# meca_2013_2.net
KiCad netlist of a schematic drawn in EAGLE
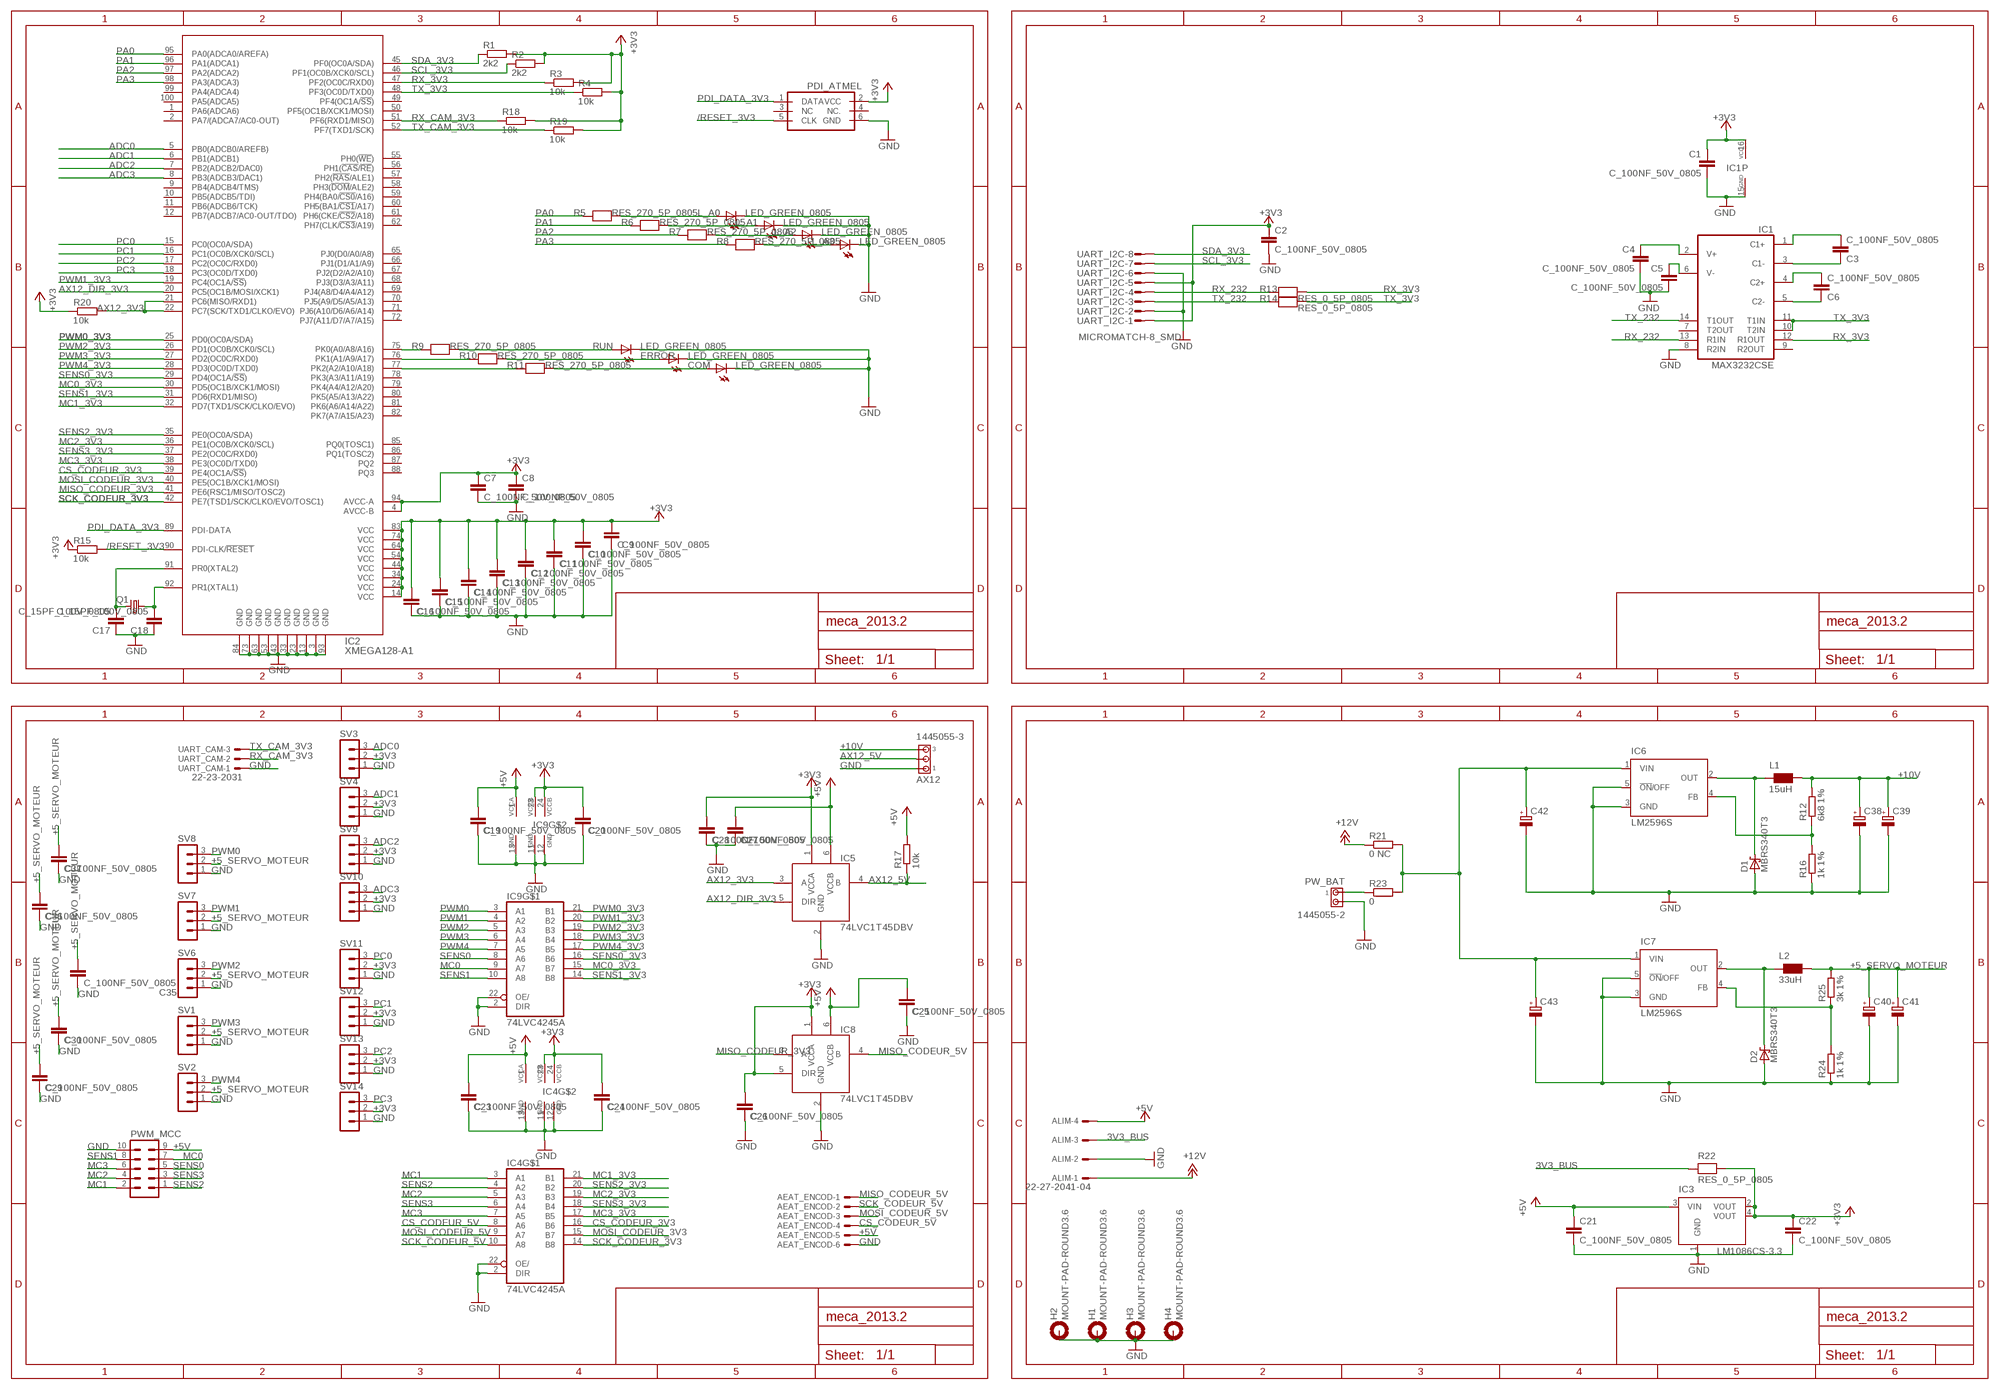
[diagram p0: schematic, sheet 1]

(export (version "E")
  (design (tool "Eeschema 10.0.6"))
  (components
    (comp (ref "AEAT_ENCOD")
      (value "22-23-2061")
      (footprint "eagle-import:22-23-2061")
      (fields (field (name "MF") "MOLEX"))
      (libsource (lib "eagle-import") (part "22-23-2061"))
    )
    (comp (ref "ALIM")
      (value "22-27-2041-04")
      (footprint "eagle-import:6410-04")
      (libsource (lib "eagle-import") (part "22-?-0427-2041"))
    )
    (comp (ref "AX12")
      (value "1445055-3")
      (footprint "eagle-import:1445055-3")
      (libsource (lib "eagle-import") (part "1445055-3"))
    )
    (comp (ref "C1")
      (value "C_100NF_50V_0805")
      (footprint "eagle-import:C0805")
      (libsource (lib "eagle-import") (part "C_100NF_50V_0805"))
    )
    (comp (ref "C2")
      (value "C_100NF_50V_0805")
      (footprint "eagle-import:C0805")
      (libsource (lib "eagle-import") (part "C_100NF_50V_0805"))
    )
    (comp (ref "C3")
      (value "C_100NF_50V_0805")
      (footprint "eagle-import:C0805")
      (libsource (lib "eagle-import") (part "C_100NF_50V_0805"))
    )
    (comp (ref "C4")
      (value "C_100NF_50V_0805")
      (footprint "eagle-import:C0805")
      (libsource (lib "eagle-import") (part "C_100NF_50V_0805"))
    )
    (comp (ref "C5")
      (value "C_100NF_50V_0805")
      (footprint "eagle-import:C0805")
      (libsource (lib "eagle-import") (part "C_100NF_50V_0805"))
    )
    (comp (ref "C6")
      (value "C_100NF_50V_0805")
      (footprint "eagle-import:C0805")
      (libsource (lib "eagle-import") (part "C_100NF_50V_0805"))
    )
    (comp (ref "C7")
      (value "C_100NF_50V_0805")
      (footprint "eagle-import:C0805")
      (libsource (lib "eagle-import") (part "C_100NF_50V_0805"))
    )
    (comp (ref "C8")
      (value "C_100NF_50V_0805")
      (footprint "eagle-import:C0805")
      (libsource (lib "eagle-import") (part "C_100NF_50V_0805"))
    )
    (comp (ref "C9")
      (value "C_100NF_50V_0805")
      (footprint "eagle-import:C0805")
      (libsource (lib "eagle-import") (part "C_100NF_50V_0805"))
    )
    (comp (ref "C10")
      (value "C_100NF_50V_0805")
      (footprint "eagle-import:C0805")
      (libsource (lib "eagle-import") (part "C_100NF_50V_0805"))
    )
    (comp (ref "C11")
      (value "C_100NF_50V_0805")
      (footprint "eagle-import:C0805")
      (libsource (lib "eagle-import") (part "C_100NF_50V_0805"))
    )
    (comp (ref "C12")
      (value "C_100NF_50V_0805")
      (footprint "eagle-import:C0805")
      (libsource (lib "eagle-import") (part "C_100NF_50V_0805"))
    )
    (comp (ref "C13")
      (value "C_100NF_50V_0805")
      (footprint "eagle-import:C0805")
      (libsource (lib "eagle-import") (part "C_100NF_50V_0805"))
    )
    (comp (ref "C14")
      (value "C_100NF_50V_0805")
      (footprint "eagle-import:C0805")
      (libsource (lib "eagle-import") (part "C_100NF_50V_0805"))
    )
    (comp (ref "C15")
      (value "C_100NF_50V_0805")
      (footprint "eagle-import:C0805")
      (libsource (lib "eagle-import") (part "C_100NF_50V_0805"))
    )
    (comp (ref "C16")
      (value "C_100NF_50V_0805")
      (footprint "eagle-import:C0805")
      (libsource (lib "eagle-import") (part "C_100NF_50V_0805"))
    )
    (comp (ref "C17")
      (value "C_15PF_100V_0805")
      (footprint "eagle-import:C0805")
      (libsource (lib "eagle-import") (part "C_15PF_100V_0805"))
    )
    (comp (ref "C18")
      (value "C_15PF_100V_0805")
      (footprint "eagle-import:C0805")
      (libsource (lib "eagle-import") (part "C_15PF_100V_0805"))
    )
    (comp (ref "C19")
      (value "C_100NF_50V_0805")
      (footprint "eagle-import:C0805")
      (libsource (lib "eagle-import") (part "C_100NF_50V_0805"))
    )
    (comp (ref "C20")
      (value "C_100NF_50V_0805")
      (footprint "eagle-import:C0805")
      (libsource (lib "eagle-import") (part "C_100NF_50V_0805"))
    )
    (comp (ref "C21")
      (value "C_100NF_50V_0805")
      (footprint "eagle-import:C0805")
      (libsource (lib "eagle-import") (part "C_100NF_50V_0805"))
    )
    (comp (ref "C22")
      (value "C_100NF_50V_0805")
      (footprint "eagle-import:C0805")
      (libsource (lib "eagle-import") (part "C_100NF_50V_0805"))
    )
    (comp (ref "C23")
      (value "C_100NF_50V_0805")
      (footprint "eagle-import:C0805")
      (libsource (lib "eagle-import") (part "C_100NF_50V_0805"))
    )
    (comp (ref "C24")
      (value "C_100NF_50V_0805")
      (footprint "eagle-import:C0805")
      (libsource (lib "eagle-import") (part "C_100NF_50V_0805"))
    )
    (comp (ref "C25")
      (value "C_100NF_50V_0805")
      (footprint "eagle-import:C0805")
      (libsource (lib "eagle-import") (part "C_100NF_50V_0805"))
    )
    (comp (ref "C26")
      (value "C_100NF_50V_0805")
      (footprint "eagle-import:C0805")
      (libsource (lib "eagle-import") (part "C_100NF_50V_0805"))
    )
    (comp (ref "C27")
      (value "C_100NF_50V_0805")
      (footprint "eagle-import:C0805")
      (libsource (lib "eagle-import") (part "C_100NF_50V_0805"))
    )
    (comp (ref "C28")
      (value "C_100NF_50V_0805")
      (footprint "eagle-import:C0805")
      (libsource (lib "eagle-import") (part "C_100NF_50V_0805"))
    )
    (comp (ref "C29")
      (value "C_100NF_50V_0805")
      (footprint "eagle-import:C0805")
      (libsource (lib "eagle-import") (part "C_100NF_50V_0805"))
    )
    (comp (ref "C30")
      (value "C_100NF_50V_0805")
      (footprint "eagle-import:C0805")
      (libsource (lib "eagle-import") (part "C_100NF_50V_0805"))
    )
    (comp (ref "C35")
      (value "C_100NF_50V_0805")
      (footprint "eagle-import:C0805")
      (libsource (lib "eagle-import") (part "C_100NF_50V_0805"))
    )
    (comp (ref "C36")
      (value "C_100NF_50V_0805")
      (footprint "eagle-import:C0805")
      (libsource (lib "eagle-import") (part "C_100NF_50V_0805"))
    )
    (comp (ref "C37")
      (value "C_100NF_50V_0805")
      (footprint "eagle-import:C0805")
      (libsource (lib "eagle-import") (part "C_100NF_50V_0805"))
    )
    (comp (ref "C38")
      (value "CPOL-EUG")
      (footprint "eagle-import:PANASONIC_G")
      (libsource (lib "eagle-import") (part "CPOL-EUG"))
    )
    (comp (ref "C39")
      (value "CPOL-EUG")
      (footprint "eagle-import:PANASONIC_G")
      (libsource (lib "eagle-import") (part "CPOL-EUG"))
    )
    (comp (ref "C40")
      (value "CPOL-EUG")
      (footprint "eagle-import:PANASONIC_G")
      (libsource (lib "eagle-import") (part "CPOL-EUG"))
    )
    (comp (ref "C41")
      (value "CPOL-EUG")
      (footprint "eagle-import:PANASONIC_G")
      (libsource (lib "eagle-import") (part "CPOL-EUG"))
    )
    (comp (ref "C42")
      (value "CPOL-EUG")
      (footprint "eagle-import:PANASONIC_G")
      (libsource (lib "eagle-import") (part "CPOL-EUG"))
    )
    (comp (ref "C43")
      (value "CPOL-EUG")
      (footprint "eagle-import:PANASONIC_G")
      (libsource (lib "eagle-import") (part "CPOL-EUG"))
    )
    (comp (ref "COM")
      (value "LED_GREEN_0805")
      (footprint "eagle-import:CHIP-LED0805")
      (libsource (lib "eagle-import") (part "LED_GREEN_0805"))
    )
    (comp (ref "D1")
      (value "MBRS340T3")
      (footprint "eagle-import:SMC")
      (libsource (lib "eagle-import") (part "MBRS30T34"))
    )
    (comp (ref "D2")
      (value "MBRS340T3")
      (footprint "eagle-import:SMC")
      (libsource (lib "eagle-import") (part "MBRS30T34"))
    )
    (comp (ref "ERROR")
      (value "LED_GREEN_0805")
      (footprint "eagle-import:CHIP-LED0805")
      (libsource (lib "eagle-import") (part "LED_GREEN_0805"))
    )
    (comp (ref "H1")
      (value "MOUNT-PAD-ROUND3.6")
      (footprint "eagle-import:3,6-PAD")
      (libsource (lib "eagle-import") (part "MOUNT-PAD-ROUND3.6"))
    )
    (comp (ref "H2")
      (value "MOUNT-PAD-ROUND3.6")
      (footprint "eagle-import:3,6-PAD")
      (libsource (lib "eagle-import") (part "MOUNT-PAD-ROUND3.6"))
    )
    (comp (ref "H3")
      (value "MOUNT-PAD-ROUND3.6")
      (footprint "eagle-import:3,6-PAD")
      (libsource (lib "eagle-import") (part "MOUNT-PAD-ROUND3.6"))
    )
    (comp (ref "H4")
      (value "MOUNT-PAD-ROUND3.6")
      (footprint "eagle-import:3,6-PAD")
      (libsource (lib "eagle-import") (part "MOUNT-PAD-ROUND3.6"))
    )
    (comp (ref "IC1")
      (value "MAX3232CSE")
      (footprint "eagle-import:SO16")
      (libsource (lib "eagle-import") (part "MAX3232SEC"))
    )
    (comp (ref "IC2")
      (value "XMEGA128-A1")
      (footprint "eagle-import:TQFP100")
      (libsource (lib "eagle-import") (part "XMEGA-A1TQFP"))
    )
    (comp (ref "IC3")
      (value "LM1086CS-3.3")
      (footprint "eagle-import:TO263")
      (libsource (lib "eagle-import") (part "LM1086CS-3.3"))
    )
    (comp (ref "IC4")
      (value "74LVC4245A")
      (footprint "eagle-import:TSSOP28")
      (libsource (lib "eagle-import") (part "74LVC4245A"))
    )
    (comp (ref "IC5")
      (value "74LVC1T45DBV")
      (footprint "eagle-import:SOT23-6")
      (libsource (lib "eagle-import") (part "74LVC1T45DBV"))
    )
    (comp (ref "IC6")
      (value "LM2596S")
      (footprint "eagle-import:TO263-5")
      (fields (field (name "MF") "NATIONAL SEMICONDUCTOR") (field (name "MPN") "LM2596S-ADJ/NOPB"))
      (libsource (lib "eagle-import") (part "LM2596S"))
    )
    (comp (ref "IC7")
      (value "LM2596S")
      (footprint "eagle-import:TO263-5")
      (fields (field (name "MF") "NATIONAL SEMICONDUCTOR") (field (name "MPN") "LM2596S-ADJ/NOPB"))
      (libsource (lib "eagle-import") (part "LM2596S"))
    )
    (comp (ref "IC8")
      (value "74LVC1T45DBV")
      (footprint "eagle-import:SOT23-6")
      (libsource (lib "eagle-import") (part "74LVC1T45DBV"))
    )
    (comp (ref "IC9")
      (value "74LVC4245A")
      (footprint "eagle-import:TSSOP28")
      (libsource (lib "eagle-import") (part "74LVC4245A"))
    )
    (comp (ref "L1")
      (value "15uH")
      (footprint "eagle-import:WE-PD_L_XL_XXL")
      (libsource (lib "eagle-import") (part "WE-PD_L/XL/XXL"))
    )
    (comp (ref "L2")
      (value "33uH")
      (footprint "eagle-import:WE-PD_L_XL_XXL")
      (libsource (lib "eagle-import") (part "WE-PD_L/XL/XXL"))
    )
    (comp (ref "L_A0")
      (value "LED_GREEN_0805")
      (footprint "eagle-import:CHIP-LED0805")
      (libsource (lib "eagle-import") (part "LED_GREEN_0805"))
    )
    (comp (ref "L_A1")
      (value "LED_GREEN_0805")
      (footprint "eagle-import:CHIP-LED0805")
      (libsource (lib "eagle-import") (part "LED_GREEN_0805"))
    )
    (comp (ref "L_A2")
      (value "LED_GREEN_0805")
      (footprint "eagle-import:CHIP-LED0805")
      (libsource (lib "eagle-import") (part "LED_GREEN_0805"))
    )
    (comp (ref "L_A3")
      (value "LED_GREEN_0805")
      (footprint "eagle-import:CHIP-LED0805")
      (libsource (lib "eagle-import") (part "LED_GREEN_0805"))
    )
    (comp (ref "PDI_ATMEL")
      (value "PDI_ATMEL")
      (footprint "eagle-import:ML6")
      (libsource (lib "eagle-import") (part "PDI_ATMEL"))
    )
    (comp (ref "PWM_MCC")
      (value "ML10")
      (footprint "eagle-import:ML10")
      (libsource (lib "eagle-import") (part "ML10"))
    )
    (comp (ref "PW_BAT")
      (value "1445055-2")
      (footprint "eagle-import:1445055-2")
      (libsource (lib "eagle-import") (part "1445055-2"))
    )
    (comp (ref "Q1")
      (value "CRYSTAL_16MHZ_HC49UP")
      (footprint "eagle-import:HC49UP")
      (libsource (lib "eagle-import") (part "CRYSTAL_16MHZ_HC49UP"))
    )
    (comp (ref "R1")
      (value "2k2")
      (footprint "eagle-import:R0603")
      (libsource (lib "eagle-import") (part "R-EU_R0603"))
    )
    (comp (ref "R2")
      (value "2k2")
      (footprint "eagle-import:R0603")
      (libsource (lib "eagle-import") (part "R-EU_R0603"))
    )
    (comp (ref "R3")
      (value "10k")
      (footprint "eagle-import:R0603")
      (libsource (lib "eagle-import") (part "R-EU_R0603"))
    )
    (comp (ref "R4")
      (value "10k")
      (footprint "eagle-import:R0603")
      (libsource (lib "eagle-import") (part "R-EU_R0603"))
    )
    (comp (ref "R5")
      (value "RES_270_5P_0805")
      (footprint "eagle-import:R0805")
      (libsource (lib "eagle-import") (part "RES_270_5P_0805"))
    )
    (comp (ref "R6")
      (value "RES_270_5P_0805")
      (footprint "eagle-import:R0805")
      (libsource (lib "eagle-import") (part "RES_270_5P_0805"))
    )
    (comp (ref "R7")
      (value "RES_270_5P_0805")
      (footprint "eagle-import:R0805")
      (libsource (lib "eagle-import") (part "RES_270_5P_0805"))
    )
    (comp (ref "R8")
      (value "RES_270_5P_0805")
      (footprint "eagle-import:R0805")
      (libsource (lib "eagle-import") (part "RES_270_5P_0805"))
    )
    (comp (ref "R9")
      (value "RES_270_5P_0805")
      (footprint "eagle-import:R0805")
      (libsource (lib "eagle-import") (part "RES_270_5P_0805"))
    )
    (comp (ref "R10")
      (value "RES_270_5P_0805")
      (footprint "eagle-import:R0805")
      (libsource (lib "eagle-import") (part "RES_270_5P_0805"))
    )
    (comp (ref "R11")
      (value "RES_270_5P_0805")
      (footprint "eagle-import:R0805")
      (libsource (lib "eagle-import") (part "RES_270_5P_0805"))
    )
    (comp (ref "R12")
      (value "6k8 1%")
      (footprint "eagle-import:R0805")
      (libsource (lib "eagle-import") (part "resistor_R-EU_R0805"))
    )
    (comp (ref "R13")
      (value "RES_0_5P_0805")
      (footprint "eagle-import:R0805")
      (libsource (lib "eagle-import") (part "RES_0_5P_0805"))
    )
    (comp (ref "R14")
      (value "RES_0_5P_0805")
      (footprint "eagle-import:R0805")
      (libsource (lib "eagle-import") (part "RES_0_5P_0805"))
    )
    (comp (ref "R15")
      (value "10k")
      (footprint "eagle-import:R0603")
      (libsource (lib "eagle-import") (part "R-EU_R0603"))
    )
    (comp (ref "R16")
      (value "1k 1%")
      (footprint "eagle-import:R0805")
      (libsource (lib "eagle-import") (part "resistor_R-EU_R0805"))
    )
    (comp (ref "R17")
      (value "10k")
      (footprint "eagle-import:R0805")
      (libsource (lib "eagle-import") (part "resistor_R-EU_R0805"))
    )
    (comp (ref "R18")
      (value "10k")
      (footprint "eagle-import:R0603")
      (libsource (lib "eagle-import") (part "R-EU_R0603"))
    )
    (comp (ref "R19")
      (value "10k")
      (footprint "eagle-import:R0603")
      (libsource (lib "eagle-import") (part "R-EU_R0603"))
    )
    (comp (ref "R20")
      (value "10k")
      (footprint "eagle-import:R0603")
      (libsource (lib "eagle-import") (part "R-EU_R0603"))
    )
    (comp (ref "R21")
      (value "0 NC")
      (footprint "eagle-import:R0805")
      (libsource (lib "eagle-import") (part "R-EU_R0805"))
    )
    (comp (ref "R22")
      (value "RES_0_5P_0805")
      (footprint "eagle-import:R0805")
      (libsource (lib "eagle-import") (part "RES_0_5P_0805"))
    )
    (comp (ref "R23")
      (value "0")
      (footprint "eagle-import:R0805")
      (libsource (lib "eagle-import") (part "R-EU_R0805"))
    )
    (comp (ref "R24")
      (value "1k 1%")
      (footprint "eagle-import:R0805")
      (libsource (lib "eagle-import") (part "R-EU_R0805"))
    )
    (comp (ref "R25")
      (value "3k 1%")
      (footprint "eagle-import:R0805")
      (libsource (lib "eagle-import") (part "R-EU_R0805"))
    )
    (comp (ref "RUN")
      (value "LED_GREEN_0805")
      (footprint "eagle-import:CHIP-LED0805")
      (libsource (lib "eagle-import") (part "LED_GREEN_0805"))
    )
    (comp (ref "SV1")
      (value "MA03-1")
      (footprint "eagle-import:MA03-1")
      (libsource (lib "eagle-import") (part "MA03-1"))
    )
    (comp (ref "SV2")
      (value "MA03-1")
      (footprint "eagle-import:MA03-1")
      (libsource (lib "eagle-import") (part "MA03-1"))
    )
    (comp (ref "SV3")
      (value "MA03-1")
      (footprint "eagle-import:MA03-1")
      (fields (field (name "OC_FARNELL") "unknown") (field (name "OC_NEWARK") "unknown"))
      (libsource (lib "eagle-import") (part "MA03-1"))
    )
    (comp (ref "SV4")
      (value "MA03-1")
      (footprint "eagle-import:MA03-1")
      (fields (field (name "OC_FARNELL") "unknown") (field (name "OC_NEWARK") "unknown"))
      (libsource (lib "eagle-import") (part "MA03-1"))
    )
    (comp (ref "SV6")
      (value "MA03-1")
      (footprint "eagle-import:MA03-1")
      (fields (field (name "OC_FARNELL") "unknown") (field (name "OC_NEWARK") "unknown"))
      (libsource (lib "eagle-import") (part "MA03-1"))
    )
    (comp (ref "SV7")
      (value "MA03-1")
      (footprint "eagle-import:MA03-1")
      (fields (field (name "OC_FARNELL") "unknown") (field (name "OC_NEWARK") "unknown"))
      (libsource (lib "eagle-import") (part "MA03-1"))
    )
    (comp (ref "SV8")
      (value "MA03-1")
      (footprint "eagle-import:MA03-1")
      (fields (field (name "OC_FARNELL") "unknown") (field (name "OC_NEWARK") "unknown"))
      (libsource (lib "eagle-import") (part "MA03-1"))
    )
    (comp (ref "SV9")
      (value "MA03-1")
      (footprint "eagle-import:MA03-1")
      (fields (field (name "OC_FARNELL") "unknown") (field (name "OC_NEWARK") "unknown"))
      (libsource (lib "eagle-import") (part "MA03-1"))
    )
    (comp (ref "SV10")
      (value "MA03-1")
      (footprint "eagle-import:MA03-1")
      (fields (field (name "OC_FARNELL") "unknown") (field (name "OC_NEWARK") "unknown"))
      (libsource (lib "eagle-import") (part "MA03-1"))
    )
    (comp (ref "SV11")
      (value "MA03-1")
      (footprint "eagle-import:MA03-1")
      (fields (field (name "OC_FARNELL") "unknown") (field (name "OC_NEWARK") "unknown"))
      (libsource (lib "eagle-import") (part "MA03-1"))
    )
    (comp (ref "SV12")
      (value "MA03-1")
      (footprint "eagle-import:MA03-1")
      (fields (field (name "OC_FARNELL") "unknown") (field (name "OC_NEWARK") "unknown"))
      (libsource (lib "eagle-import") (part "MA03-1"))
    )
    (comp (ref "SV13")
      (value "MA03-1")
      (footprint "eagle-import:MA03-1")
      (fields (field (name "OC_FARNELL") "unknown") (field (name "OC_NEWARK") "unknown"))
      (libsource (lib "eagle-import") (part "MA03-1"))
    )
    (comp (ref "SV14")
      (value "MA03-1")
      (footprint "eagle-import:MA03-1")
      (fields (field (name "OC_FARNELL") "unknown") (field (name "OC_NEWARK") "unknown"))
      (libsource (lib "eagle-import") (part "MA03-1"))
    )
    (comp (ref "UART_CAM")
      (value "22-23-2031")
      (footprint "eagle-import:22-23-2031")
      (fields (field (name "MF") "MOLEX"))
      (libsource (lib "eagle-import") (part "22-23-2031"))
    )
    (comp (ref "UART_I2C")
      (value "MICROMATCH-8_SMD")
      (footprint "eagle-import:MICROMATCH-8_SMD")
      (libsource (lib "eagle-import") (part "MICROMATCH-8_SMD"))
    )
  )
  (nets
    (net (code "1") (name "+3V3") (class "Default")
      (node (ref "C1") (pin "1") (pinfunction "1_1") (pintype "passive"))
      (node (ref "C10") (pin "1") (pinfunction "1_1") (pintype "passive"))
      (node (ref "C11") (pin "1") (pinfunction "1_1") (pintype "passive"))
      (node (ref "C12") (pin "1") (pinfunction "1_1") (pintype "passive"))
      (node (ref "C13") (pin "1") (pinfunction "1_1") (pintype "passive"))
      (node (ref "C14") (pin "1") (pinfunction "1_1") (pintype "passive"))
      (node (ref "C15") (pin "1") (pinfunction "1_1") (pintype "passive"))
      (node (ref "C16") (pin "1") (pinfunction "1_1") (pintype "passive"))
      (node (ref "C2") (pin "1") (pinfunction "1_1") (pintype "passive"))
      (node (ref "C20") (pin "1") (pinfunction "1_1") (pintype "passive"))
      (node (ref "C22") (pin "1") (pinfunction "1_1") (pintype "passive"))
      (node (ref "C24") (pin "1") (pinfunction "1_1") (pintype "passive"))
      (node (ref "C26") (pin "1") (pinfunction "1_1") (pintype "passive"))
      (node (ref "C28") (pin "1") (pinfunction "1_1") (pintype "passive"))
      (node (ref "C7") (pin "1") (pinfunction "1_1") (pintype "passive"))
      (node (ref "C8") (pin "1") (pinfunction "1_1") (pintype "passive"))
      (node (ref "C9") (pin "1") (pinfunction "1_1") (pintype "passive"))
      (node (ref "IC1") (pin "16") (pinfunction "VCC_16") (pintype "power_in"))
      (node (ref "IC2") (pin "14") (pinfunction "VCC_14") (pintype "power_in"))
      (node (ref "IC2") (pin "24") (pinfunction "VCC_24") (pintype "power_in"))
      (node (ref "IC2") (pin "34") (pinfunction "VCC_34") (pintype "power_in"))
      (node (ref "IC2") (pin "4") (pinfunction "AVCC-B_4") (pintype "power_in"))
      (node (ref "IC2") (pin "44") (pinfunction "VCC_44") (pintype "power_in"))
      (node (ref "IC2") (pin "54") (pinfunction "VCC_54") (pintype "power_in"))
      (node (ref "IC2") (pin "64") (pinfunction "VCC_64") (pintype "power_in"))
      (node (ref "IC2") (pin "74") (pinfunction "VCC_74") (pintype "power_in"))
      (node (ref "IC2") (pin "83") (pinfunction "VCC_83") (pintype "power_in"))
      (node (ref "IC2") (pin "94") (pinfunction "AVCC-A_94") (pintype "power_in"))
      (node (ref "IC3") (pin "2") (pinfunction "VOUT_2") (pintype "bidirectional"))
      (node (ref "IC3") (pin "4") (pinfunction "VOUT_4") (pintype "bidirectional"))
      (node (ref "IC4") (pin "23") (pinfunction "VCCB_23") (pintype "power_in"))
      (node (ref "IC4") (pin "24") (pinfunction "VCCB_24") (pintype "power_in"))
      (node (ref "IC5") (pin "1") (pinfunction "VCCA_1") (pintype "power_in"))
      (node (ref "IC8") (pin "1") (pinfunction "VCCA_1") (pintype "power_in"))
      (node (ref "IC8") (pin "5") (pinfunction "DIR_5") (pintype "input"))
      (node (ref "IC9") (pin "23") (pinfunction "VCCB_23") (pintype "power_in"))
      (node (ref "IC9") (pin "24") (pinfunction "VCCB_24") (pintype "power_in"))
      (node (ref "PDI_ATMEL") (pin "2") (pinfunction "VCC_2") (pintype "passive"))
      (node (ref "R1") (pin "2") (pinfunction "2_2") (pintype "passive"))
      (node (ref "R15") (pin "1") (pinfunction "1_1") (pintype "passive"))
      (node (ref "R18") (pin "2") (pinfunction "2_2") (pintype "passive"))
      (node (ref "R19") (pin "2") (pinfunction "2_2") (pintype "passive"))
      (node (ref "R2") (pin "2") (pinfunction "2_2") (pintype "passive"))
      (node (ref "R20") (pin "1") (pinfunction "1_1") (pintype "passive"))
      (node (ref "R22") (pin "2") (pinfunction "2_2") (pintype "bidirectional"))
      (node (ref "R3") (pin "2") (pinfunction "2_2") (pintype "passive"))
      (node (ref "R4") (pin "2") (pinfunction "2_2") (pintype "passive"))
      (node (ref "SV10") (pin "2") (pinfunction "2_2") (pintype "passive"))
      (node (ref "SV11") (pin "2") (pinfunction "2_2") (pintype "passive"))
      (node (ref "SV12") (pin "2") (pinfunction "2_2") (pintype "passive"))
      (node (ref "SV13") (pin "2") (pinfunction "2_2") (pintype "passive"))
      (node (ref "SV14") (pin "2") (pinfunction "2_2") (pintype "passive"))
      (node (ref "SV3") (pin "2") (pinfunction "2_2") (pintype "passive"))
      (node (ref "SV4") (pin "2") (pinfunction "2_2") (pintype "passive"))
      (node (ref "SV9") (pin "2") (pinfunction "2_2") (pintype "passive"))
      (node (ref "UART_I2C") (pin "1") (pinfunction "S_1") (pintype "passive"))
      (node (ref "UART_I2C") (pin "5") (pinfunction "S_5") (pintype "passive"))
    )
    (net (code "2") (name "+5V") (class "Default")
      (node (ref "AEAT_ENCOD") (pin "5") (pinfunction "S_5") (pintype "passive"))
      (node (ref "ALIM") (pin "4") (pinfunction "S_4") (pintype "passive"))
      (node (ref "C19") (pin "1") (pinfunction "1_1") (pintype "passive"))
      (node (ref "C21") (pin "1") (pinfunction "1_1") (pintype "passive"))
      (node (ref "C23") (pin "1") (pinfunction "1_1") (pintype "passive"))
      (node (ref "C25") (pin "1") (pinfunction "1_1") (pintype "passive"))
      (node (ref "C27") (pin "1") (pinfunction "1_1") (pintype "passive"))
      (node (ref "IC3") (pin "3") (pinfunction "VIN_3") (pintype "bidirectional"))
      (node (ref "IC4") (pin "1") (pinfunction "VCCA_1") (pintype "power_in"))
      (node (ref "IC5") (pin "6") (pinfunction "VCCB_6") (pintype "power_in"))
      (node (ref "IC8") (pin "6") (pinfunction "VCCB_6") (pintype "power_in"))
      (node (ref "IC9") (pin "1") (pinfunction "VCCA_1") (pintype "power_in"))
      (node (ref "PWM_MCC") (pin "9") (pinfunction "9_9") (pintype "passive"))
      (node (ref "R17") (pin "2") (pinfunction "2_2") (pintype "passive"))
    )
    (net (code "3") (name "+12V") (class "Default")
      (node (ref "ALIM") (pin "1") (pinfunction "S_1") (pintype "passive"))
      (node (ref "R21") (pin "1") (pinfunction "1_1") (pintype "passive"))
    )
    (net (code "4") (name "/+5_SERVO_MOTEUR") (class "Default")
      (node (ref "C29") (pin "1") (pinfunction "1_1") (pintype "passive"))
      (node (ref "C30") (pin "1") (pinfunction "1_1") (pintype "passive"))
      (node (ref "C35") (pin "1") (pinfunction "1_1") (pintype "passive"))
      (node (ref "C36") (pin "1") (pinfunction "1_1") (pintype "passive"))
      (node (ref "C37") (pin "1") (pinfunction "1_1") (pintype "passive"))
      (node (ref "C40") (pin "+") (pinfunction "+_+") (pintype "passive"))
      (node (ref "C41") (pin "+") (pinfunction "+_+") (pintype "passive"))
      (node (ref "L2") (pin "1") (pinfunction "2_1") (pintype "passive"))
      (node (ref "R25") (pin "2") (pinfunction "2_2") (pintype "passive"))
      (node (ref "SV1") (pin "2") (pinfunction "2_2") (pintype "passive"))
      (node (ref "SV2") (pin "2") (pinfunction "2_2") (pintype "passive"))
      (node (ref "SV6") (pin "2") (pinfunction "2_2") (pintype "passive"))
      (node (ref "SV7") (pin "2") (pinfunction "2_2") (pintype "passive"))
      (node (ref "SV8") (pin "2") (pinfunction "2_2") (pintype "passive"))
    )
    (net (code "5") (name "/+10V") (class "Default")
      (node (ref "AX12") (pin "3") (pinfunction "3_3") (pintype "passive"))
      (node (ref "C38") (pin "+") (pinfunction "+_+") (pintype "passive"))
      (node (ref "C39") (pin "+") (pinfunction "+_+") (pintype "passive"))
      (node (ref "L1") (pin "1") (pinfunction "2_1") (pintype "passive"))
      (node (ref "R12") (pin "2") (pinfunction "2_2") (pintype "passive"))
    )
    (net (code "6") (name "/3V3_BUS") (class "Default")
      (node (ref "ALIM") (pin "3") (pinfunction "S_3") (pintype "passive"))
      (node (ref "R22") (pin "1") (pinfunction "1_1") (pintype "bidirectional"))
    )
    (net (code "7") (name "/ADC0") (class "Default")
      (node (ref "IC2") (pin "5") (pinfunction "PB0(ADCB0/AREFB)_5") (pintype "bidirectional"))
      (node (ref "SV3") (pin "3") (pinfunction "3_3") (pintype "passive"))
    )
    (net (code "8") (name "/ADC1") (class "Default")
      (node (ref "IC2") (pin "6") (pinfunction "PB1(ADCB1)_6") (pintype "bidirectional"))
      (node (ref "SV4") (pin "3") (pinfunction "3_3") (pintype "passive"))
    )
    (net (code "9") (name "/ADC2") (class "Default")
      (node (ref "IC2") (pin "7") (pinfunction "PB2(ADCB2/DAC0)_7") (pintype "bidirectional"))
      (node (ref "SV9") (pin "3") (pinfunction "3_3") (pintype "passive"))
    )
    (net (code "10") (name "/ADC3") (class "Default")
      (node (ref "IC2") (pin "8") (pinfunction "PB3(ADCB3/DAC1)_8") (pintype "bidirectional"))
      (node (ref "SV10") (pin "3") (pinfunction "3_3") (pintype "passive"))
    )
    (net (code "11") (name "/AX12_3V3") (class "Default")
      (node (ref "IC2") (pin "21") (pinfunction "PC6(MISO/RXD1)_21") (pintype "bidirectional"))
      (node (ref "IC2") (pin "22") (pinfunction "PC7(SCK/TXD1/CLKO/EVO)_22") (pintype "bidirectional"))
      (node (ref "IC5") (pin "3") (pinfunction "A_3") (pintype "bidirectional"))
      (node (ref "R20") (pin "2") (pinfunction "2_2") (pintype "passive"))
    )
    (net (code "12") (name "/AX12_5V") (class "Default")
      (node (ref "AX12") (pin "2") (pinfunction "2_2") (pintype "passive"))
      (node (ref "IC5") (pin "4") (pinfunction "B_4") (pintype "bidirectional"))
      (node (ref "R17") (pin "1") (pinfunction "1_1") (pintype "passive"))
    )
    (net (code "13") (name "/AX12_DIR_3V3") (class "Default")
      (node (ref "IC2") (pin "20") (pinfunction "PC5(OC1B/MOSI/XCK1)_20") (pintype "bidirectional"))
      (node (ref "IC5") (pin "5") (pinfunction "DIR_5") (pintype "input"))
    )
    (net (code "14") (name "/CS_CODEUR_3V3") (class "Default")
      (node (ref "IC2") (pin "39") (pinfunction "PE4(OC1A/~{SS})_39") (pintype "bidirectional"))
      (node (ref "IC4") (pin "16") (pinfunction "B6_16") (pintype "bidirectional"))
    )
    (net (code "15") (name "/CS_CODEUR_5V") (class "Default")
      (node (ref "AEAT_ENCOD") (pin "4") (pinfunction "S_4") (pintype "passive"))
      (node (ref "IC4") (pin "8") (pinfunction "A6_8") (pintype "bidirectional"))
    )
    (net (code "16") (name "/MC0") (class "Default")
      (node (ref "IC9") (pin "9") (pinfunction "A7_9") (pintype "bidirectional"))
      (node (ref "PWM_MCC") (pin "7") (pinfunction "7_7") (pintype "passive"))
    )
    (net (code "17") (name "/MC0_3V3") (class "Default")
      (node (ref "IC2") (pin "30") (pinfunction "PD5(OC1B/XCK1/MOSI)_30") (pintype "bidirectional"))
      (node (ref "IC9") (pin "15") (pinfunction "B7_15") (pintype "bidirectional"))
    )
    (net (code "18") (name "/MC1") (class "Default")
      (node (ref "IC4") (pin "3") (pinfunction "A1_3") (pintype "bidirectional"))
      (node (ref "PWM_MCC") (pin "2") (pinfunction "2_2") (pintype "passive"))
    )
    (net (code "19") (name "/MC1_3V3") (class "Default")
      (node (ref "IC2") (pin "32") (pinfunction "PD7(TXD1/SCK/CLKO/EVO)_32") (pintype "bidirectional"))
      (node (ref "IC4") (pin "21") (pinfunction "B1_21") (pintype "bidirectional"))
    )
    (net (code "20") (name "/MC2") (class "Default")
      (node (ref "IC4") (pin "5") (pinfunction "A3_5") (pintype "bidirectional"))
      (node (ref "PWM_MCC") (pin "4") (pinfunction "4_4") (pintype "passive"))
    )
    (net (code "21") (name "/MC2_3V3") (class "Default")
      (node (ref "IC2") (pin "36") (pinfunction "PE1(OC0B/XCK0/SCL)_36") (pintype "bidirectional"))
      (node (ref "IC4") (pin "19") (pinfunction "B3_19") (pintype "bidirectional"))
    )
    (net (code "22") (name "/MC3") (class "Default")
      (node (ref "IC4") (pin "7") (pinfunction "A5_7") (pintype "bidirectional"))
      (node (ref "PWM_MCC") (pin "6") (pinfunction "6_6") (pintype "passive"))
    )
    (net (code "23") (name "/MC3_3V3") (class "Default")
      (node (ref "IC2") (pin "38") (pinfunction "PE3(OC0D/TXD0)_38") (pintype "bidirectional"))
      (node (ref "IC4") (pin "17") (pinfunction "B5_17") (pintype "bidirectional"))
    )
    (net (code "24") (name "/MISO_CODEUR_3V3") (class "Default")
      (node (ref "IC2") (pin "41") (pinfunction "PE6(RSC1/MISO/TOSC2)_41") (pintype "bidirectional"))
      (node (ref "IC8") (pin "3") (pinfunction "A_3") (pintype "bidirectional"))
    )
    (net (code "25") (name "/MISO_CODEUR_5V") (class "Default")
      (node (ref "AEAT_ENCOD") (pin "1") (pinfunction "S_1") (pintype "passive"))
      (node (ref "IC8") (pin "4") (pinfunction "B_4") (pintype "bidirectional"))
    )
    (net (code "26") (name "/MOSI_CODEUR_3V3") (class "Default")
      (node (ref "IC2") (pin "40") (pinfunction "PE5(OC1B/XCK1/MOSI)_40") (pintype "bidirectional"))
      (node (ref "IC4") (pin "15") (pinfunction "B7_15") (pintype "bidirectional"))
    )
    (net (code "27") (name "/MOSI_CODEUR_5V") (class "Default")
      (node (ref "AEAT_ENCOD") (pin "3") (pinfunction "S_3") (pintype "passive"))
      (node (ref "IC4") (pin "9") (pinfunction "A7_9") (pintype "bidirectional"))
    )
    (net (code "28") (name "/PA0") (class "Default")
      (node (ref "IC2") (pin "95") (pinfunction "PA0(ADCA0/AREFA)_95") (pintype "bidirectional"))
      (node (ref "R5") (pin "1") (pinfunction "1_1") (pintype "bidirectional"))
    )
    (net (code "29") (name "/PA1") (class "Default")
      (node (ref "IC2") (pin "96") (pinfunction "PA1(ADCA1)_96") (pintype "bidirectional"))
      (node (ref "R6") (pin "1") (pinfunction "1_1") (pintype "bidirectional"))
    )
    (net (code "30") (name "/PA2") (class "Default")
      (node (ref "IC2") (pin "97") (pinfunction "PA2(ADCA2)_97") (pintype "bidirectional"))
      (node (ref "R7") (pin "1") (pinfunction "1_1") (pintype "bidirectional"))
    )
    (net (code "31") (name "/PA3") (class "Default")
      (node (ref "IC2") (pin "98") (pinfunction "PA3(ADCA3)_98") (pintype "bidirectional"))
      (node (ref "R8") (pin "1") (pinfunction "1_1") (pintype "bidirectional"))
    )
    (net (code "32") (name "/PC0") (class "Default")
      (node (ref "IC2") (pin "15") (pinfunction "PC0(OC0A/SDA)_15") (pintype "bidirectional"))
      (node (ref "SV11") (pin "3") (pinfunction "3_3") (pintype "passive"))
    )
    (net (code "33") (name "/PC1") (class "Default")
      (node (ref "IC2") (pin "16") (pinfunction "PC1(OC0B/XCK0/SCL)_16") (pintype "bidirectional"))
      (node (ref "SV12") (pin "3") (pinfunction "3_3") (pintype "passive"))
    )
    (net (code "34") (name "/PC2") (class "Default")
      (node (ref "IC2") (pin "17") (pinfunction "PC2(OC0C/RXD0)_17") (pintype "bidirectional"))
      (node (ref "SV13") (pin "3") (pinfunction "3_3") (pintype "passive"))
    )
    (net (code "35") (name "/PC3") (class "Default")
      (node (ref "IC2") (pin "18") (pinfunction "PC3(OC0D/TXD0)_18") (pintype "bidirectional"))
      (node (ref "SV14") (pin "3") (pinfunction "3_3") (pintype "passive"))
    )
    (net (code "36") (name "/PDI_DATA_3V3") (class "Default")
      (node (ref "IC2") (pin "89") (pinfunction "PDI-DATA_89") (pintype "bidirectional"))
      (node (ref "PDI_ATMEL") (pin "1") (pinfunction "DATA_1") (pintype "passive"))
    )
    (net (code "37") (name "/PWM0") (class "Default")
      (node (ref "IC9") (pin "3") (pinfunction "A1_3") (pintype "bidirectional"))
      (node (ref "SV8") (pin "3") (pinfunction "3_3") (pintype "passive"))
    )
    (net (code "38") (name "/PWM0_3V3") (class "Default")
      (node (ref "IC2") (pin "25") (pinfunction "PD0(OC0A/SDA)_25") (pintype "bidirectional"))
      (node (ref "IC9") (pin "21") (pinfunction "B1_21") (pintype "bidirectional"))
    )
    (net (code "39") (name "/PWM1") (class "Default")
      (node (ref "IC9") (pin "4") (pinfunction "A2_4") (pintype "bidirectional"))
      (node (ref "SV7") (pin "3") (pinfunction "3_3") (pintype "passive"))
    )
    (net (code "40") (name "/PWM1_3V3") (class "Default")
      (node (ref "IC2") (pin "19") (pinfunction "PC4(OC1A/~{SS})_19") (pintype "bidirectional"))
      (node (ref "IC9") (pin "20") (pinfunction "B2_20") (pintype "bidirectional"))
    )
    (net (code "41") (name "/PWM2") (class "Default")
      (node (ref "IC9") (pin "5") (pinfunction "A3_5") (pintype "bidirectional"))
      (node (ref "SV6") (pin "3") (pinfunction "3_3") (pintype "passive"))
    )
    (net (code "42") (name "/PWM2_3V3") (class "Default")
      (node (ref "IC2") (pin "26") (pinfunction "PD1(OC0B/XCK0/SCL)_26") (pintype "bidirectional"))
      (node (ref "IC9") (pin "19") (pinfunction "B3_19") (pintype "bidirectional"))
    )
    (net (code "43") (name "/PWM3") (class "Default")
      (node (ref "IC9") (pin "6") (pinfunction "A4_6") (pintype "bidirectional"))
      (node (ref "SV1") (pin "3") (pinfunction "3_3") (pintype "passive"))
    )
    (net (code "44") (name "/PWM3_3V3") (class "Default")
      (node (ref "IC2") (pin "27") (pinfunction "PD2(OC0C/RXD0)_27") (pintype "bidirectional"))
      (node (ref "IC9") (pin "18") (pinfunction "B4_18") (pintype "bidirectional"))
    )
    (net (code "45") (name "/PWM4") (class "Default")
      (node (ref "IC9") (pin "7") (pinfunction "A5_7") (pintype "bidirectional"))
      (node (ref "SV2") (pin "3") (pinfunction "3_3") (pintype "passive"))
    )
    (net (code "46") (name "/PWM4_3V3") (class "Default")
      (node (ref "IC2") (pin "28") (pinfunction "PD3(OC0D/TXD0)_28") (pintype "bidirectional"))
      (node (ref "IC9") (pin "17") (pinfunction "B5_17") (pintype "bidirectional"))
    )
    (net (code "47") (name "/RX_3V3") (class "Default")
      (node (ref "IC1") (pin "12") (pinfunction "R1OUT_12") (pintype "output"))
      (node (ref "IC2") (pin "47") (pinfunction "PF2(OC0C/RXD0)_47") (pintype "bidirectional"))
      (node (ref "R13") (pin "2") (pinfunction "2_2") (pintype "bidirectional"))
      (node (ref "R3") (pin "1") (pinfunction "1_1") (pintype "passive"))
    )
    (net (code "48") (name "/RX_232") (class "Default")
      (node (ref "IC1") (pin "13") (pinfunction "R1IN_13") (pintype "input"))
      (node (ref "R13") (pin "1") (pinfunction "1_1") (pintype "bidirectional"))
      (node (ref "UART_I2C") (pin "4") (pinfunction "S_4") (pintype "passive"))
    )
    (net (code "49") (name "/RX_CAM_3V3") (class "Default")
      (node (ref "IC2") (pin "51") (pinfunction "PF6(RXD1/MISO)_51") (pintype "bidirectional"))
      (node (ref "R18") (pin "1") (pinfunction "1_1") (pintype "passive"))
      (node (ref "UART_CAM") (pin "2") (pinfunction "S_2") (pintype "passive"))
    )
    (net (code "50") (name "/SCK_CODEUR_3V3") (class "Default")
      (node (ref "IC2") (pin "42") (pinfunction "PE7(TSD1/SCK/CLKO/EVO/TOSC1)_42") (pintype "bidirectional"))
      (node (ref "IC4") (pin "14") (pinfunction "B8_14") (pintype "bidirectional"))
    )
    (net (code "51") (name "/SCK_CODEUR_5V") (class "Default")
      (node (ref "AEAT_ENCOD") (pin "2") (pinfunction "S_2") (pintype "passive"))
      (node (ref "IC4") (pin "10") (pinfunction "A8_10") (pintype "bidirectional"))
    )
    (net (code "52") (name "/SCL_3V3") (class "Default")
      (node (ref "IC2") (pin "46") (pinfunction "PF1(OC0B/XCK0/SCL)_46") (pintype "bidirectional"))
      (node (ref "R2") (pin "1") (pinfunction "1_1") (pintype "passive"))
      (node (ref "UART_I2C") (pin "7") (pinfunction "S_7") (pintype "passive"))
    )
    (net (code "53") (name "/SDA_3V3") (class "Default")
      (node (ref "IC2") (pin "45") (pinfunction "PF0(OC0A/SDA)_45") (pintype "bidirectional"))
      (node (ref "R1") (pin "1") (pinfunction "1_1") (pintype "passive"))
      (node (ref "UART_I2C") (pin "8") (pinfunction "S_8") (pintype "passive"))
    )
    (net (code "54") (name "/SENS0") (class "Default")
      (node (ref "IC9") (pin "8") (pinfunction "A6_8") (pintype "bidirectional"))
      (node (ref "PWM_MCC") (pin "5") (pinfunction "5_5") (pintype "passive"))
    )
    (net (code "55") (name "/SENS0_3V3") (class "Default")
      (node (ref "IC2") (pin "29") (pinfunction "PD4(OC1A/~{SS})_29") (pintype "bidirectional"))
      (node (ref "IC9") (pin "16") (pinfunction "B6_16") (pintype "bidirectional"))
    )
    (net (code "56") (name "/SENS1") (class "Default")
      (node (ref "IC9") (pin "10") (pinfunction "A8_10") (pintype "bidirectional"))
      (node (ref "PWM_MCC") (pin "8") (pinfunction "8_8") (pintype "passive"))
    )
    (net (code "57") (name "/SENS1_3V3") (class "Default")
      (node (ref "IC2") (pin "31") (pinfunction "PD6(RXD1/MISO)_31") (pintype "bidirectional"))
      (node (ref "IC9") (pin "14") (pinfunction "B8_14") (pintype "bidirectional"))
    )
    (net (code "58") (name "/SENS2") (class "Default")
      (node (ref "IC4") (pin "4") (pinfunction "A2_4") (pintype "bidirectional"))
      (node (ref "PWM_MCC") (pin "1") (pinfunction "1_1") (pintype "passive"))
    )
    (net (code "59") (name "/SENS2_3V3") (class "Default")
      (node (ref "IC2") (pin "35") (pinfunction "PE0(OC0A/SDA)_35") (pintype "bidirectional"))
      (node (ref "IC4") (pin "20") (pinfunction "B2_20") (pintype "bidirectional"))
    )
    (net (code "60") (name "/SENS3") (class "Default")
      (node (ref "IC4") (pin "6") (pinfunction "A4_6") (pintype "bidirectional"))
      (node (ref "PWM_MCC") (pin "3") (pinfunction "3_3") (pintype "passive"))
    )
    (net (code "61") (name "/SENS3_3V3") (class "Default")
      (node (ref "IC2") (pin "37") (pinfunction "PE2(OC0C/RXD0)_37") (pintype "bidirectional"))
      (node (ref "IC4") (pin "18") (pinfunction "B4_18") (pintype "bidirectional"))
    )
    (net (code "62") (name "/TX_3V3") (class "Default")
      (node (ref "IC1") (pin "10") (pinfunction "T2IN_10") (pintype "input"))
      (node (ref "IC1") (pin "11") (pinfunction "T1IN_11") (pintype "input"))
      (node (ref "IC2") (pin "48") (pinfunction "PF3(OC0D/TXD0)_48") (pintype "bidirectional"))
      (node (ref "R14") (pin "2") (pinfunction "2_2") (pintype "bidirectional"))
      (node (ref "R4") (pin "1") (pinfunction "1_1") (pintype "passive"))
    )
    (net (code "63") (name "/TX_232") (class "Default")
      (node (ref "IC1") (pin "14") (pinfunction "T1OUT_14") (pintype "output"))
      (node (ref "R14") (pin "1") (pinfunction "1_1") (pintype "bidirectional"))
      (node (ref "UART_I2C") (pin "3") (pinfunction "S_3") (pintype "passive"))
    )
    (net (code "64") (name "/TX_CAM_3V3") (class "Default")
      (node (ref "IC2") (pin "52") (pinfunction "PF7(TXD1/SCK)_52") (pintype "bidirectional"))
      (node (ref "R19") (pin "1") (pinfunction "1_1") (pintype "passive"))
      (node (ref "UART_CAM") (pin "3") (pinfunction "S_3") (pintype "passive"))
    )
    (net (code "65") (name "/{slash}RESET_3V3") (class "Default")
      (node (ref "IC2") (pin "90") (pinfunction "PDI-CLK/~{RESET}_90") (pintype "input"))
      (node (ref "PDI_ATMEL") (pin "5") (pinfunction "CLK_5") (pintype "passive"))
      (node (ref "R15") (pin "2") (pinfunction "2_2") (pintype "passive"))
    )
    (net (code "66") (name "GND") (class "Default")
      (node (ref "AEAT_ENCOD") (pin "6") (pinfunction "S_6") (pintype "passive"))
      (node (ref "ALIM") (pin "2") (pinfunction "S_2") (pintype "passive"))
      (node (ref "AX12") (pin "1") (pinfunction "1_1") (pintype "passive"))
      (node (ref "C1") (pin "2") (pinfunction "2_2") (pintype "passive"))
      (node (ref "C10") (pin "2") (pinfunction "2_2") (pintype "passive"))
      (node (ref "C11") (pin "2") (pinfunction "2_2") (pintype "passive"))
      (node (ref "C12") (pin "2") (pinfunction "2_2") (pintype "passive"))
      (node (ref "C13") (pin "2") (pinfunction "2_2") (pintype "passive"))
      (node (ref "C14") (pin "2") (pinfunction "2_2") (pintype "passive"))
      (node (ref "C15") (pin "2") (pinfunction "2_2") (pintype "passive"))
      (node (ref "C16") (pin "2") (pinfunction "2_2") (pintype "passive"))
      (node (ref "C17") (pin "1") (pinfunction "1_1") (pintype "passive"))
      (node (ref "C18") (pin "1") (pinfunction "1_1") (pintype "passive"))
      (node (ref "C19") (pin "2") (pinfunction "2_2") (pintype "passive"))
      (node (ref "C2") (pin "2") (pinfunction "2_2") (pintype "passive"))
      (node (ref "C20") (pin "2") (pinfunction "2_2") (pintype "passive"))
      (node (ref "C21") (pin "2") (pinfunction "2_2") (pintype "passive"))
      (node (ref "C22") (pin "2") (pinfunction "2_2") (pintype "passive"))
      (node (ref "C23") (pin "2") (pinfunction "2_2") (pintype "passive"))
      (node (ref "C24") (pin "2") (pinfunction "2_2") (pintype "passive"))
      (node (ref "C25") (pin "2") (pinfunction "2_2") (pintype "passive"))
      (node (ref "C26") (pin "2") (pinfunction "2_2") (pintype "passive"))
      (node (ref "C27") (pin "2") (pinfunction "2_2") (pintype "passive"))
      (node (ref "C28") (pin "2") (pinfunction "2_2") (pintype "passive"))
      (node (ref "C29") (pin "2") (pinfunction "2_2") (pintype "passive"))
      (node (ref "C30") (pin "2") (pinfunction "2_2") (pintype "passive"))
      (node (ref "C35") (pin "2") (pinfunction "2_2") (pintype "passive"))
      (node (ref "C36") (pin "2") (pinfunction "2_2") (pintype "passive"))
      (node (ref "C37") (pin "2") (pinfunction "2_2") (pintype "passive"))
      (node (ref "C38") (pin "-") (pinfunction "-_-") (pintype "passive"))
      (node (ref "C39") (pin "-") (pinfunction "-_-") (pintype "passive"))
      (node (ref "C4") (pin "2") (pinfunction "2_2") (pintype "passive"))
      (node (ref "C40") (pin "-") (pinfunction "-_-") (pintype "passive"))
      (node (ref "C41") (pin "-") (pinfunction "-_-") (pintype "passive"))
      (node (ref "C42") (pin "-") (pinfunction "-_-") (pintype "passive"))
      (node (ref "C43") (pin "-") (pinfunction "-_-") (pintype "passive"))
      (node (ref "C5") (pin "2") (pinfunction "2_2") (pintype "passive"))
      (node (ref "C7") (pin "2") (pinfunction "2_2") (pintype "passive"))
      (node (ref "C8") (pin "2") (pinfunction "2_2") (pintype "passive"))
      (node (ref "C9") (pin "2") (pinfunction "2_2") (pintype "passive"))
      (node (ref "COM") (pin "C") (pinfunction "C_C") (pintype "passive"))
      (node (ref "D1") (pin "A") (pinfunction "A_A") (pintype "passive"))
      (node (ref "D2") (pin "A") (pinfunction "A_A") (pintype "passive"))
      (node (ref "ERROR") (pin "C") (pinfunction "C_C") (pintype "passive"))
      (node (ref "H1") (pin "B3,6") (pinfunction "MOUNT_B3,6") (pintype "passive"))
      (node (ref "H2") (pin "B3,6") (pinfunction "MOUNT_B3,6") (pintype "passive"))
      (node (ref "H3") (pin "B3,6") (pinfunction "MOUNT_B3,6") (pintype "passive"))
      (node (ref "H4") (pin "B3,6") (pinfunction "MOUNT_B3,6") (pintype "passive"))
      (node (ref "IC1") (pin "15") (pinfunction "GND_15") (pintype "power_in"))
      (node (ref "IC1") (pin "8") (pinfunction "R2IN_8") (pintype "input"))
      (node (ref "IC2") (pin "13") (pinfunction "GND_13") (pintype "power_in"))
      (node (ref "IC2") (pin "23") (pinfunction "GND_23") (pintype "power_in"))
      (node (ref "IC2") (pin "3") (pinfunction "GND_3") (pintype "power_in"))
      (node (ref "IC2") (pin "33") (pinfunction "GND_33") (pintype "power_in"))
      (node (ref "IC2") (pin "43") (pinfunction "GND_43") (pintype "power_in"))
      (node (ref "IC2") (pin "53") (pinfunction "GND_53") (pintype "power_in"))
      (node (ref "IC2") (pin "63") (pinfunction "GND_63") (pintype "power_in"))
      (node (ref "IC2") (pin "73") (pinfunction "GND_73") (pintype "power_in"))
      (node (ref "IC2") (pin "84") (pinfunction "GND_84") (pintype "power_in"))
      (node (ref "IC2") (pin "93") (pinfunction "GND_93") (pintype "power_in"))
      (node (ref "IC3") (pin "1") (pinfunction "GND_1") (pintype "bidirectional"))
      (node (ref "IC4") (pin "11") (pinfunction "GND_11") (pintype "power_in"))
      (node (ref "IC4") (pin "12") (pinfunction "GND_12") (pintype "power_in"))
      (node (ref "IC4") (pin "13") (pinfunction "GND_13") (pintype "power_in"))
      (node (ref "IC4") (pin "2") (pinfunction "DIR_2") (pintype "input"))
      (node (ref "IC4") (pin "22") (pinfunction "OE/_22") (pintype "input"))
      (node (ref "IC5") (pin "2") (pinfunction "GND_2") (pintype "power_in"))
      (node (ref "IC6") (pin "3") (pinfunction "GND_3") (pintype "power_in"))
      (node (ref "IC6") (pin "5") (pinfunction "~{ON}/OFF_5") (pintype "input"))
      (node (ref "IC7") (pin "3") (pinfunction "GND_3") (pintype "power_in"))
      (node (ref "IC7") (pin "5") (pinfunction "~{ON}/OFF_5") (pintype "input"))
      (node (ref "IC8") (pin "2") (pinfunction "GND_2") (pintype "power_in"))
      (node (ref "IC9") (pin "11") (pinfunction "GND_11") (pintype "power_in"))
      (node (ref "IC9") (pin "12") (pinfunction "GND_12") (pintype "power_in"))
      (node (ref "IC9") (pin "13") (pinfunction "GND_13") (pintype "power_in"))
      (node (ref "IC9") (pin "2") (pinfunction "DIR_2") (pintype "input"))
      (node (ref "IC9") (pin "22") (pinfunction "OE/_22") (pintype "input"))
      (node (ref "L_A0") (pin "C") (pinfunction "C_C") (pintype "passive"))
      (node (ref "L_A1") (pin "C") (pinfunction "C_C") (pintype "passive"))
      (node (ref "L_A2") (pin "C") (pinfunction "C_C") (pintype "passive"))
      (node (ref "L_A3") (pin "C") (pinfunction "C_C") (pintype "passive"))
      (node (ref "PDI_ATMEL") (pin "6") (pinfunction "GND_6") (pintype "passive"))
      (node (ref "PWM_MCC") (pin "10") (pinfunction "10_10") (pintype "passive"))
      (node (ref "PW_BAT") (pin "2") (pinfunction "2_2") (pintype "passive"))
      (node (ref "R16") (pin "1") (pinfunction "1_1") (pintype "passive"))
      (node (ref "R24") (pin "1") (pinfunction "1_1") (pintype "passive"))
      (node (ref "RUN") (pin "C") (pinfunction "C_C") (pintype "passive"))
      (node (ref "SV1") (pin "1") (pinfunction "1_1") (pintype "passive"))
      (node (ref "SV10") (pin "1") (pinfunction "1_1") (pintype "passive"))
      (node (ref "SV11") (pin "1") (pinfunction "1_1") (pintype "passive"))
      (node (ref "SV12") (pin "1") (pinfunction "1_1") (pintype "passive"))
      (node (ref "SV13") (pin "1") (pinfunction "1_1") (pintype "passive"))
      (node (ref "SV14") (pin "1") (pinfunction "1_1") (pintype "passive"))
      (node (ref "SV2") (pin "1") (pinfunction "1_1") (pintype "passive"))
      (node (ref "SV3") (pin "1") (pinfunction "1_1") (pintype "passive"))
      (node (ref "SV4") (pin "1") (pinfunction "1_1") (pintype "passive"))
      (node (ref "SV6") (pin "1") (pinfunction "1_1") (pintype "passive"))
      (node (ref "SV7") (pin "1") (pinfunction "1_1") (pintype "passive"))
      (node (ref "SV8") (pin "1") (pinfunction "1_1") (pintype "passive"))
      (node (ref "SV9") (pin "1") (pinfunction "1_1") (pintype "passive"))
      (node (ref "UART_CAM") (pin "1") (pinfunction "S_1") (pintype "passive"))
      (node (ref "UART_I2C") (pin "2") (pinfunction "S_2") (pintype "passive"))
      (node (ref "UART_I2C") (pin "6") (pinfunction "S_6") (pintype "passive"))
    )
    (net (code "67") (name "Net-(COM-PadA)") (class "Default")
      (node (ref "COM") (pin "A") (pinfunction "A_A") (pintype "passive"))
      (node (ref "R11") (pin "2") (pinfunction "2_2") (pintype "bidirectional"))
    )
    (net (code "68") (name "Net-(ERROR-PadA)") (class "Default")
      (node (ref "ERROR") (pin "A") (pinfunction "A_A") (pintype "passive"))
      (node (ref "R10") (pin "2") (pinfunction "2_2") (pintype "bidirectional"))
    )
    (net (code "69") (name "Net-(IC1A-C1+)") (class "Default")
      (node (ref "C3") (pin "1") (pinfunction "1_1") (pintype "passive"))
      (node (ref "IC1") (pin "1") (pinfunction "C1+_1") (pintype "bidirectional"))
    )
    (net (code "70") (name "Net-(IC1A-C1-)") (class "Default")
      (node (ref "C3") (pin "2") (pinfunction "2_2") (pintype "passive"))
      (node (ref "IC1") (pin "3") (pinfunction "C1-_3") (pintype "bidirectional"))
    )
    (net (code "71") (name "Net-(IC1A-C2+)") (class "Default")
      (node (ref "C6") (pin "1") (pinfunction "1_1") (pintype "passive"))
      (node (ref "IC1") (pin "4") (pinfunction "C2+_4") (pintype "bidirectional"))
    )
    (net (code "72") (name "Net-(IC1A-C2-)") (class "Default")
      (node (ref "C6") (pin "2") (pinfunction "2_2") (pintype "passive"))
      (node (ref "IC1") (pin "5") (pinfunction "C2-_5") (pintype "bidirectional"))
    )
    (net (code "73") (name "Net-(IC1A-V+)") (class "Default")
      (node (ref "C4") (pin "1") (pinfunction "1_1") (pintype "passive"))
      (node (ref "IC1") (pin "2") (pinfunction "V+_2") (pintype "bidirectional"))
    )
    (net (code "74") (name "Net-(IC1A-V-)") (class "Default")
      (node (ref "C5") (pin "1") (pinfunction "1_1") (pintype "passive"))
      (node (ref "IC1") (pin "6") (pinfunction "V-_6") (pintype "bidirectional"))
    )
    (net (code "75") (name "Net-(IC2-PK0(A0{slash}A8{slash}A16))") (class "Default")
      (node (ref "IC2") (pin "75") (pinfunction "PK0(A0/A8/A16)_75") (pintype "bidirectional"))
      (node (ref "R9") (pin "1") (pinfunction "1_1") (pintype "bidirectional"))
    )
    (net (code "76") (name "Net-(IC2-PK1(A1{slash}A9{slash}A17))") (class "Default")
      (node (ref "IC2") (pin "76") (pinfunction "PK1(A1/A9/A17)_76") (pintype "bidirectional"))
      (node (ref "R10") (pin "1") (pinfunction "1_1") (pintype "bidirectional"))
    )
    (net (code "77") (name "Net-(IC2-PK2(A2{slash}A10{slash}A18))") (class "Default")
      (node (ref "IC2") (pin "77") (pinfunction "PK2(A2/A10/A18)_77") (pintype "bidirectional"))
      (node (ref "R11") (pin "1") (pinfunction "1_1") (pintype "bidirectional"))
    )
    (net (code "78") (name "Net-(IC2-PR0(XTAL2))") (class "Default")
      (node (ref "C17") (pin "2") (pinfunction "2_2") (pintype "passive"))
      (node (ref "IC2") (pin "91") (pinfunction "PR0(XTAL2)_91") (pintype "bidirectional"))
      (node (ref "Q1") (pin "2") (pinfunction "2_2") (pintype "passive"))
    )
    (net (code "79") (name "Net-(IC2-PR1(XTAL1))") (class "Default")
      (node (ref "C18") (pin "2") (pinfunction "2_2") (pintype "passive"))
      (node (ref "IC2") (pin "92") (pinfunction "PR1(XTAL1)_92") (pintype "bidirectional"))
      (node (ref "Q1") (pin "1") (pinfunction "1_1") (pintype "passive"))
    )
    (net (code "80") (name "Net-(IC6-FB)") (class "Default")
      (node (ref "IC6") (pin "4") (pinfunction "FB_4") (pintype "input"))
      (node (ref "R12") (pin "1") (pinfunction "1_1") (pintype "passive"))
      (node (ref "R16") (pin "2") (pinfunction "2_2") (pintype "passive"))
    )
    (net (code "81") (name "Net-(IC6-OUT)") (class "Default")
      (node (ref "D1") (pin "C") (pinfunction "C_C") (pintype "passive"))
      (node (ref "IC6") (pin "2") (pinfunction "OUT_2") (pintype "output"))
      (node (ref "L1") (pin "2") (pinfunction "1_2") (pintype "passive"))
    )
    (net (code "82") (name "Net-(IC6-VIN)") (class "Default")
      (node (ref "C42") (pin "+") (pinfunction "+_+") (pintype "passive"))
      (node (ref "C43") (pin "+") (pinfunction "+_+") (pintype "passive"))
      (node (ref "IC6") (pin "1") (pinfunction "VIN_1") (pintype "input"))
      (node (ref "IC7") (pin "1") (pinfunction "VIN_1") (pintype "input"))
      (node (ref "R21") (pin "2") (pinfunction "2_2") (pintype "passive"))
      (node (ref "R23") (pin "2") (pinfunction "2_2") (pintype "passive"))
    )
    (net (code "83") (name "Net-(IC7-FB)") (class "Default")
      (node (ref "IC7") (pin "4") (pinfunction "FB_4") (pintype "input"))
      (node (ref "R24") (pin "2") (pinfunction "2_2") (pintype "passive"))
      (node (ref "R25") (pin "1") (pinfunction "1_1") (pintype "passive"))
    )
    (net (code "84") (name "Net-(IC7-OUT)") (class "Default")
      (node (ref "D2") (pin "C") (pinfunction "C_C") (pintype "passive"))
      (node (ref "IC7") (pin "2") (pinfunction "OUT_2") (pintype "output"))
      (node (ref "L2") (pin "2") (pinfunction "1_2") (pintype "passive"))
    )
    (net (code "85") (name "Net-(L_A0-PadA)") (class "Default")
      (node (ref "L_A0") (pin "A") (pinfunction "A_A") (pintype "passive"))
      (node (ref "R5") (pin "2") (pinfunction "2_2") (pintype "bidirectional"))
    )
    (net (code "86") (name "Net-(L_A1-PadA)") (class "Default")
      (node (ref "L_A1") (pin "A") (pinfunction "A_A") (pintype "passive"))
      (node (ref "R6") (pin "2") (pinfunction "2_2") (pintype "bidirectional"))
    )
    (net (code "87") (name "Net-(L_A2-PadA)") (class "Default")
      (node (ref "L_A2") (pin "A") (pinfunction "A_A") (pintype "passive"))
      (node (ref "R7") (pin "2") (pinfunction "2_2") (pintype "bidirectional"))
    )
    (net (code "88") (name "Net-(L_A3-PadA)") (class "Default")
      (node (ref "L_A3") (pin "A") (pinfunction "A_A") (pintype "passive"))
      (node (ref "R8") (pin "2") (pinfunction "2_2") (pintype "bidirectional"))
    )
    (net (code "89") (name "Net-(PW_BAT-Pad1)") (class "Default")
      (node (ref "PW_BAT") (pin "1") (pinfunction "1_1") (pintype "passive"))
      (node (ref "R23") (pin "1") (pinfunction "1_1") (pintype "passive"))
    )
    (net (code "90") (name "Net-(R9-Pad2)") (class "Default")
      (node (ref "R9") (pin "2") (pinfunction "2_2") (pintype "bidirectional"))
      (node (ref "RUN") (pin "A") (pinfunction "A_A") (pintype "passive"))
    )
    (net (code "91") (name "unconnected-(IC1A-R2OUT-Pad9)") (class "Default")
      (node (ref "IC1") (pin "9") (pinfunction "R2OUT_9") (pintype "output"))
    )
    (net (code "92") (name "unconnected-(IC1A-T2OUT-Pad7)") (class "Default")
      (node (ref "IC1") (pin "7") (pinfunction "T2OUT_7") (pintype "output"))
    )
    (net (code "93") (name "unconnected-(IC2-PA4(ADCA4)-Pad99)") (class "Default")
      (node (ref "IC2") (pin "99") (pinfunction "PA4(ADCA4)_99") (pintype "bidirectional"))
    )
    (net (code "94") (name "unconnected-(IC2-PA5(ADCA5)-Pad100)") (class "Default")
      (node (ref "IC2") (pin "100") (pinfunction "PA5(ADCA5)_100") (pintype "bidirectional"))
    )
    (net (code "95") (name "unconnected-(IC2-PA6(ADCA6)-Pad1)") (class "Default")
      (node (ref "IC2") (pin "1") (pinfunction "PA6(ADCA6)_1") (pintype "bidirectional"))
    )
    (net (code "96") (name "unconnected-(IC2-PA7{slash}(ADCA7{slash}AC0-OUT)-Pad2)") (class "Default")
      (node (ref "IC2") (pin "2") (pinfunction "PA7/(ADCA7/AC0-OUT)_2") (pintype "bidirectional"))
    )
    (net (code "97") (name "unconnected-(IC2-PB4(ADCB4{slash}TMS)-Pad9)") (class "Default")
      (node (ref "IC2") (pin "9") (pinfunction "PB4(ADCB4/TMS)_9") (pintype "bidirectional"))
    )
    (net (code "98") (name "unconnected-(IC2-PB5(ADCB5{slash}TDI)-Pad10)") (class "Default")
      (node (ref "IC2") (pin "10") (pinfunction "PB5(ADCB5/TDI)_10") (pintype "bidirectional"))
    )
    (net (code "99") (name "unconnected-(IC2-PB6(ADCB6{slash}TCK)-Pad11)") (class "Default")
      (node (ref "IC2") (pin "11") (pinfunction "PB6(ADCB6/TCK)_11") (pintype "bidirectional"))
    )
    (net (code "100") (name "unconnected-(IC2-PB7(ADCB7{slash}AC0-OUT{slash}TDO)-Pad12)") (class "Default")
      (node (ref "IC2") (pin "12") (pinfunction "PB7(ADCB7/AC0-OUT/TDO)_12") (pintype "bidirectional"))
    )
    (net (code "101") (name "unconnected-(IC2-PF4(OC1A{slash}~{SS})-Pad49)") (class "Default")
      (node (ref "IC2") (pin "49") (pinfunction "PF4(OC1A/~{SS})_49") (pintype "bidirectional"))
    )
    (net (code "102") (name "unconnected-(IC2-PF5(OC1B{slash}XCK1{slash}MOSI)-Pad50)") (class "Default")
      (node (ref "IC2") (pin "50") (pinfunction "PF5(OC1B/XCK1/MOSI)_50") (pintype "bidirectional"))
    )
    (net (code "103") (name "unconnected-(IC2-PH0(~{WE})-Pad55)") (class "Default")
      (node (ref "IC2") (pin "55") (pinfunction "PH0(~{WE})_55") (pintype "bidirectional"))
    )
    (net (code "104") (name "unconnected-(IC2-PH1(~{CAS}{slash}~{RE})-Pad56)") (class "Default")
      (node (ref "IC2") (pin "56") (pinfunction "PH1(~{CAS}/~{RE})_56") (pintype "bidirectional"))
    )
    (net (code "105") (name "unconnected-(IC2-PH2(~{RAS}{slash}ALE1)-Pad57)") (class "Default")
      (node (ref "IC2") (pin "57") (pinfunction "PH2(~{RAS}/ALE1)_57") (pintype "bidirectional"))
    )
    (net (code "106") (name "unconnected-(IC2-PH3(~{DOM}{slash}ALE2)-Pad58)") (class "Default")
      (node (ref "IC2") (pin "58") (pinfunction "PH3(~{DOM}/ALE2)_58") (pintype "bidirectional"))
    )
    (net (code "107") (name "unconnected-(IC2-PH4(BA0{slash}~{CS0}{slash}A16)-Pad59)") (class "Default")
      (node (ref "IC2") (pin "59") (pinfunction "PH4(BA0/~{CS0}/A16)_59") (pintype "bidirectional"))
    )
    (net (code "108") (name "unconnected-(IC2-PH5(BA1{slash}~{CS1}{slash}A17)-Pad60)") (class "Default")
      (node (ref "IC2") (pin "60") (pinfunction "PH5(BA1/~{CS1}/A17)_60") (pintype "bidirectional"))
    )
    (net (code "109") (name "unconnected-(IC2-PH6(CKE{slash}~{CS2}{slash}A18)-Pad61)") (class "Default")
      (node (ref "IC2") (pin "61") (pinfunction "PH6(CKE/~{CS2}/A18)_61") (pintype "bidirectional"))
    )
    (net (code "110") (name "unconnected-(IC2-PH7(CLK{slash}~{CS3}{slash}A19)-Pad62)") (class "Default")
      (node (ref "IC2") (pin "62") (pinfunction "PH7(CLK/~{CS3}/A19)_62") (pintype "bidirectional"))
    )
    (net (code "111") (name "unconnected-(IC2-PJ0(D0{slash}A0{slash}A8)-Pad65)") (class "Default")
      (node (ref "IC2") (pin "65") (pinfunction "PJ0(D0/A0/A8)_65") (pintype "bidirectional"))
    )
    (net (code "112") (name "unconnected-(IC2-PJ1(D1{slash}A1{slash}A9)-Pad66)") (class "Default")
      (node (ref "IC2") (pin "66") (pinfunction "PJ1(D1/A1/A9)_66") (pintype "bidirectional"))
    )
    (net (code "113") (name "unconnected-(IC2-PJ2(D2{slash}A2{slash}A10)-Pad67)") (class "Default")
      (node (ref "IC2") (pin "67") (pinfunction "PJ2(D2/A2/A10)_67") (pintype "bidirectional"))
    )
    (net (code "114") (name "unconnected-(IC2-PJ3(D3{slash}A3{slash}A11)-Pad68)") (class "Default")
      (node (ref "IC2") (pin "68") (pinfunction "PJ3(D3/A3/A11)_68") (pintype "bidirectional"))
    )
    (net (code "115") (name "unconnected-(IC2-PJ4(A8{slash}D4{slash}A4{slash}A12)-Pad69)") (class "Default")
      (node (ref "IC2") (pin "69") (pinfunction "PJ4(A8/D4/A4/A12)_69") (pintype "bidirectional"))
    )
    (net (code "116") (name "unconnected-(IC2-PJ5(A9{slash}D5{slash}A5{slash}A13)-Pad70)") (class "Default")
      (node (ref "IC2") (pin "70") (pinfunction "PJ5(A9/D5/A5/A13)_70") (pintype "bidirectional"))
    )
    (net (code "117") (name "unconnected-(IC2-PJ6(A10{slash}D6{slash}A6{slash}A14)-Pad71)") (class "Default")
      (node (ref "IC2") (pin "71") (pinfunction "PJ6(A10/D6/A6/A14)_71") (pintype "bidirectional"))
    )
    (net (code "118") (name "unconnected-(IC2-PJ7(A11{slash}D7{slash}A7{slash}A15)-Pad72)") (class "Default")
      (node (ref "IC2") (pin "72") (pinfunction "PJ7(A11/D7/A7/A15)_72") (pintype "bidirectional"))
    )
    (net (code "119") (name "unconnected-(IC2-PK3(A3{slash}A11{slash}A19)-Pad78)") (class "Default")
      (node (ref "IC2") (pin "78") (pinfunction "PK3(A3/A11/A19)_78") (pintype "bidirectional"))
    )
    (net (code "120") (name "unconnected-(IC2-PK4(A4{slash}A12{slash}A20)-Pad79)") (class "Default")
      (node (ref "IC2") (pin "79") (pinfunction "PK4(A4/A12/A20)_79") (pintype "bidirectional"))
    )
    (net (code "121") (name "unconnected-(IC2-PK5(A5{slash}A13{slash}A22)-Pad80)") (class "Default")
      (node (ref "IC2") (pin "80") (pinfunction "PK5(A5/A13/A22)_80") (pintype "bidirectional"))
    )
    (net (code "122") (name "unconnected-(IC2-PK6(A6{slash}A14{slash}A22)-Pad81)") (class "Default")
      (node (ref "IC2") (pin "81") (pinfunction "PK6(A6/A14/A22)_81") (pintype "bidirectional"))
    )
    (net (code "123") (name "unconnected-(IC2-PK7(A7{slash}A15{slash}A23)-Pad82)") (class "Default")
      (node (ref "IC2") (pin "82") (pinfunction "PK7(A7/A15/A23)_82") (pintype "bidirectional"))
    )
    (net (code "124") (name "unconnected-(IC2-PQ0(TOSC1)-Pad85)") (class "Default")
      (node (ref "IC2") (pin "85") (pinfunction "PQ0(TOSC1)_85") (pintype "bidirectional"))
    )
    (net (code "125") (name "unconnected-(IC2-PQ1(TOSC2)-Pad86)") (class "Default")
      (node (ref "IC2") (pin "86") (pinfunction "PQ1(TOSC2)_86") (pintype "bidirectional"))
    )
    (net (code "126") (name "unconnected-(IC2-PQ2-Pad87)") (class "Default")
      (node (ref "IC2") (pin "87") (pinfunction "PQ2_87") (pintype "bidirectional"))
    )
    (net (code "127") (name "unconnected-(IC2-PQ3-Pad88)") (class "Default")
      (node (ref "IC2") (pin "88") (pinfunction "PQ3_88") (pintype "bidirectional"))
    )
    (net (code "128") (name "unconnected-(PDI_ATMEL-NC-Pad3)") (class "Default")
      (node (ref "PDI_ATMEL") (pin "3") (pinfunction "NC_3") (pintype "passive"))
    )
    (net (code "129") (name "unconnected-(PDI_ATMEL-NC.-Pad4)") (class "Default")
      (node (ref "PDI_ATMEL") (pin "4") (pinfunction "NC._4") (pintype "passive"))
    )
  )
)
